# schematic.net
KiCad netlist of a schematic drawn in Altium Designer
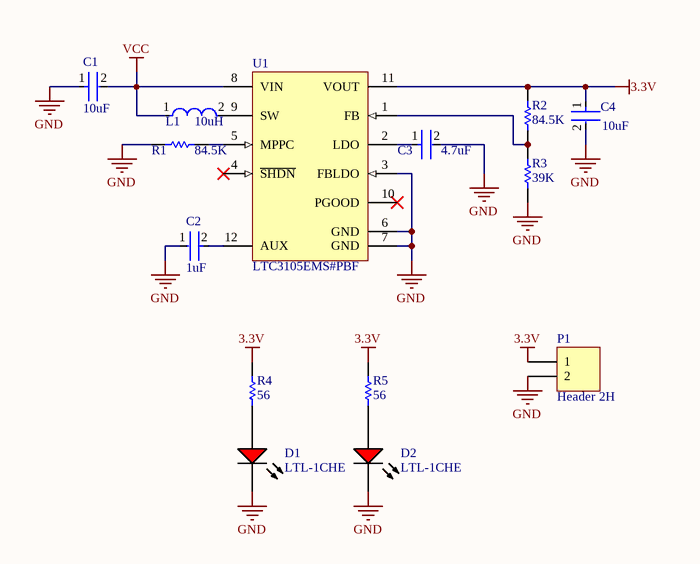
[diagram p0: schematic.SchDoc]

(export (version "E")
  (design (tool "Eeschema 10.0.6"))
  (components
    (comp (ref "C1")
      (value "10uF")
      (footprint "FP-GRM188-0_1-e0_2_0_55-IPC_A")
      (description "Chip Multilayer Ceramic Capacitors for General Purpose, 0603, 10uF, X5R, 15%, 20%, 6.3V")
      (fields (field (name "VOLTAGE") "6.3V") (field (name "TOLERANCE") "20%"))
      (libsource (lib "Altium Content Vault") (part "02cd4be3c70576c341d710602a673aa"))
    )
    (comp (ref "C2")
      (value "1uF")
      (footprint "FP-C1608-080-0_1-IPC_B")
      (description "Multilayer Ceramic Capacitors 1μF ±10% 50V X5R SMD 0603")
      (fields (field (name "VOLTAGE") "50V") (field (name "TOLERANCE") "10%"))
      (libsource (lib "Altium Content Vault") (part "236180d848d6139a670b325ea6854c9"))
    )
    (comp (ref "C3")
      (value "4.7uF")
      (footprint "FP-GRM188-0_15-IPC_C")
      (description "Chip Multilayer Ceramic Capacitors for General Purpose, 0603, 4.7uF, X5R, 15%, 10%, 25V")
      (fields (field (name "VOLTAGE") "25V") (field (name "TOLERANCE") "10%"))
      (libsource (lib "Altium Content Vault") (part "02cd4be3c70576c341d710602a673aa"))
    )
    (comp (ref "C4")
      (value "10uF")
      (footprint "FP-GRM188-0_1-e0_2_0_55-IPC_A")
      (description "Chip Multilayer Ceramic Capacitors for General Purpose, 0603, 10uF, X5R, 15%, 20%, 6.3V")
      (fields (field (name "VOLTAGE") "6.3V") (field (name "TOLERANCE") "20%"))
      (libsource (lib "Altium Content Vault") (part "02cd4be3c70576c341d710602a673aa"))
    )
    (comp (ref "D1")
      (value "LTL-1CHE")
      (footprint "INDPR60-254-520X380X650")
      (description "Radial LED, 12.6 mcd, 20 mA, 2 V, -55 to 100 degC, 2-Pin THD, RoHS, Bulk")
      (fields (field (name "TOLERANCE") "20%"))
      (libsource (lib "Altium Content Vault") (part "LED-RED-AK-2"))
    )
    (comp (ref "D2")
      (value "LTL-1CHE")
      (footprint "INDPR60-254-520X380X650")
      (description "Radial LED, 12.6 mcd, 20 mA, 2 V, -55 to 100 degC, 2-Pin THD, RoHS, Bulk")
      (fields (field (name "TOLERANCE") "20%"))
      (libsource (lib "Altium Content Vault") (part "LED-RED-AK-2"))
    )
    (comp (ref "L1")
      (value "10uH")
      (footprint "FP-NR6028-MFG")
      (description "SMD Power Inductors 10uH ±20% 1.9A 84.5mΩ")
      (fields (field (name "TOLERANCE") "20%"))
      (libsource (lib "Altium Content Vault") (part "725321dda6339637d4d059423bc1c3c"))
    )
    (comp (ref "P1")
      (value "Header 2H")
      (footprint "HDR1X2H")
      (description "Header, 2-Pin, Right Angle")
      (fields (field (name "PUBLISHER") "Altium Limited"))
      (libsource (lib "The Art and Science of PCB Design - IAP 2023") (part "Header 2H"))
    )
    (comp (ref "R1")
      (value "84.5K")
      (footprint "RESC1608X55X30LL15T15")
      (fields (field (name "PART NUMBER") "ERJ-3EKF8452V") (field (name "MANUFACTURER") "Panasonic"))
      (libsource (lib "Altium Content Vault") (part "RES"))
    )
    (comp (ref "R2")
      (value "84.5K")
      (footprint "RESC1608X55X30LL15T15")
      (fields (field (name "PART NUMBER") "ERJ-3EKF8452V") (field (name "MANUFACTURER") "Panasonic"))
      (libsource (lib "Altium Content Vault") (part "RES"))
    )
    (comp (ref "R3")
      (value "39K")
      (footprint "RESC1608X55X25LL10T15")
      (description "Chip Resistor, 39 KOhm, +/- 1%, 0.1 W, -55 to 155 degC, 0603 (1608 Metric), RoHS, Tape and Reel")
      (fields (field (name "TOLERANCE") "1%") (field (name "MANUFACTURER") "Yageo"))
      (libsource (lib "Altium Content Vault") (part "RES-2"))
    )
    (comp (ref "R4")
      (value "56")
      (footprint "RESC1608X55X30NL15T15")
      (fields (field (name "MANUFACTURER") "Panasonic") (field (name "PART NUMBER") "ERJ3EKF56R0V"))
      (libsource (lib "Altium Content Vault") (part "RES"))
    )
    (comp (ref "R5")
      (value "56")
      (footprint "RESC1608X55X30NL15T15")
      (fields (field (name "MANUFACTURER") "Panasonic") (field (name "PART NUMBER") "ERJ3EKF56R0V"))
      (libsource (lib "Altium Content Vault") (part "RES"))
    )
    (comp (ref "U1")
      (value "LTC3105EMS#PBF")
      (footprint "LT-MS-12_N")
      (fields (field (name "MANUFACTURER") "Linear Technology"))
      (libsource (lib "Altium Content Vault") (part "LT-LTC3105-MS-12"))
    )
  )
  (nets
    (net (code "1") (name "3.3V") (class "Default")
      (node (ref "C4") (pin "1") (pinfunction "1_1") (pintype "passive"))
      (node (ref "P1") (pin "1") (pinfunction "1_1") (pintype "passive"))
      (node (ref "R2") (pin "2") (pinfunction "2_2") (pintype "passive"))
      (node (ref "R4") (pin "1") (pinfunction "1_1") (pintype "passive"))
      (node (ref "R5") (pin "1") (pinfunction "1_1") (pintype "passive"))
      (node (ref "U1") (pin "11") (pinfunction "VOUT_11") (pintype "power_in"))
    )
    (net (code "2") (name "GND") (class "Default")
      (node (ref "C1") (pin "1") (pinfunction "1_1") (pintype "passive"))
      (node (ref "C2") (pin "1") (pinfunction "1_1") (pintype "passive"))
      (node (ref "C3") (pin "2") (pinfunction "2_2") (pintype "passive"))
      (node (ref "C4") (pin "2") (pinfunction "2_2") (pintype "passive"))
      (node (ref "D1") (pin "2") (pinfunction "K_2") (pintype "passive"))
      (node (ref "D2") (pin "2") (pinfunction "K_2") (pintype "passive"))
      (node (ref "P1") (pin "2") (pinfunction "2_2") (pintype "passive"))
      (node (ref "R1") (pin "1") (pinfunction "1_1") (pintype "passive"))
      (node (ref "R3") (pin "2") (pinfunction "2_2") (pintype "passive"))
      (node (ref "U1") (pin "3") (pinfunction "FBLDO_3") (pintype "input"))
      (node (ref "U1") (pin "6") (pinfunction "GND_6") (pintype "power_in"))
      (node (ref "U1") (pin "7") (pinfunction "GND_7") (pintype "power_in"))
    )
    (net (code "3") (name "Net-(D1-A)") (class "Default")
      (node (ref "D1") (pin "1") (pinfunction "A_1") (pintype "passive"))
      (node (ref "R4") (pin "2") (pinfunction "2_2") (pintype "passive"))
    )
    (net (code "4") (name "Net-(D2-A)") (class "Default")
      (node (ref "D2") (pin "1") (pinfunction "A_1") (pintype "passive"))
      (node (ref "R5") (pin "2") (pinfunction "2_2") (pintype "passive"))
    )
    (net (code "5") (name "Net-(U1-AUX)") (class "Default")
      (node (ref "C2") (pin "2") (pinfunction "2_2") (pintype "passive"))
      (node (ref "U1") (pin "12") (pinfunction "AUX_12") (pintype "power_in"))
    )
    (net (code "6") (name "Net-(U1-FB)") (class "Default")
      (node (ref "R2") (pin "1") (pinfunction "1_1") (pintype "passive"))
      (node (ref "R3") (pin "1") (pinfunction "1_1") (pintype "passive"))
      (node (ref "U1") (pin "1") (pinfunction "FB_1") (pintype "input"))
    )
    (net (code "7") (name "Net-(U1-LDO)") (class "Default")
      (node (ref "C3") (pin "1") (pinfunction "1_1") (pintype "passive"))
      (node (ref "U1") (pin "2") (pinfunction "LDO_2") (pintype "power_in"))
    )
    (net (code "8") (name "Net-(U1-MPPC)") (class "Default")
      (node (ref "R1") (pin "2") (pinfunction "2_2") (pintype "passive"))
      (node (ref "U1") (pin "5") (pinfunction "MPPC_5") (pintype "input"))
    )
    (net (code "9") (name "Net-(U1-SW)") (class "Default")
      (node (ref "L1") (pin "2") (pinfunction "2_2") (pintype "passive"))
      (node (ref "U1") (pin "9") (pinfunction "SW_9") (pintype "power_in"))
    )
    (net (code "10") (name "VCC") (class "Default")
      (node (ref "C1") (pin "2") (pinfunction "2_2") (pintype "passive"))
      (node (ref "L1") (pin "1") (pinfunction "1_1") (pintype "passive"))
      (node (ref "U1") (pin "8") (pinfunction "VIN_8") (pintype "power_in"))
    )
    (net (code "11") (name "unconnected-(U1-PGOOD-Pad10)") (class "Default")
      (node (ref "U1") (pin "10") (pinfunction "PGOOD_10") (pintype "open_collector+no_connect"))
    )
    (net (code "12") (name "unconnected-(U1-~{SHDN}-Pad4)") (class "Default")
      (node (ref "U1") (pin "4") (pinfunction "~{SHDN}_4") (pintype "input+no_connect"))
    )
  )
)
